# Charging_Circuit.net
KiCad netlist of a schematic drawn in EAGLE
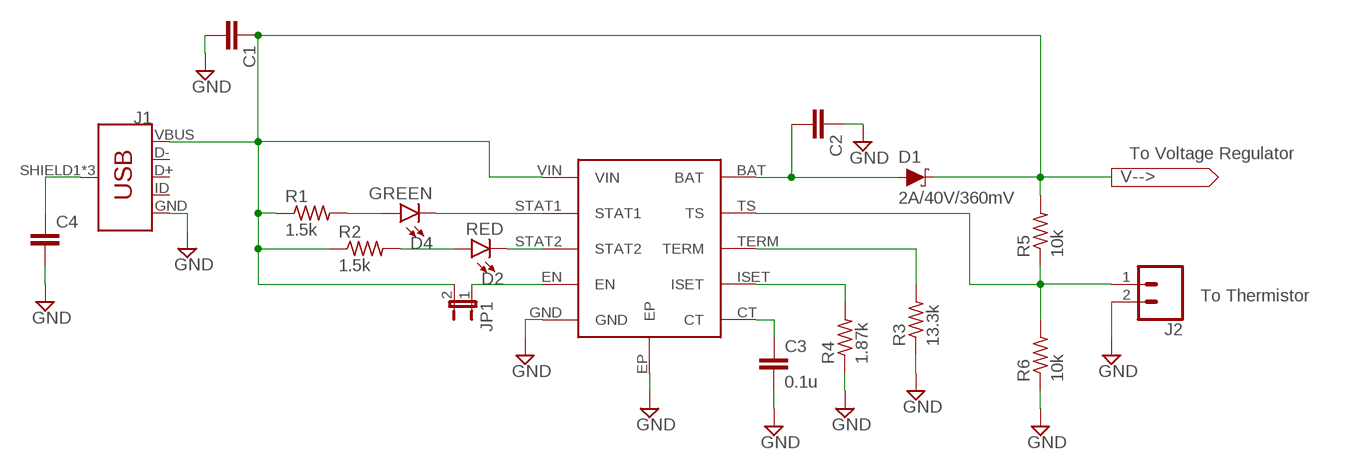
[diagram p0: schematic, sheet 1]

(export (version "E")
  (design (tool "Eeschema 10.0.6"))
  (components
    (comp (ref "C1")
      (value "C-EU025-024X044")
      (footprint "eagle-import:C025-024X044")
      (libsource (lib "eagle-import") (part "C-EU025-024X044"))
    )
    (comp (ref "C2")
      (value "C-EU025-024X044")
      (footprint "eagle-import:C025-024X044")
      (libsource (lib "eagle-import") (part "C-EU025-024X044"))
    )
    (comp (ref "C3")
      (value "0.1u")
      (footprint "eagle-import:C025-024X044")
      (libsource (lib "eagle-import") (part "C-EU025-024X044"))
    )
    (comp (ref "C4")
      (value "C-EU025-024X044")
      (footprint "eagle-import:C025-024X044")
      (libsource (lib "eagle-import") (part "C-EU025-024X044"))
    )
    (comp (ref "D1")
      (value "2A/40V/360mV")
      (footprint "eagle-import:SMA-DIODE")
      (libsource (lib "eagle-import") (part "DIODE-SCHOTTKY-B340A"))
    )
    (comp (ref "D2")
      (value "RED")
      (footprint "eagle-import:LED-1206")
      (libsource (lib "eagle-import") (part "LED-RED1206"))
    )
    (comp (ref "D4")
      (value "GREEN")
      (footprint "eagle-import:LED-1206")
      (libsource (lib "eagle-import") (part "LED-GREEN1206"))
    )
    (comp (ref "J1")
      (value "USB_MICRO-BREDUCED_PASTE")
      (footprint "eagle-import:USB-B-MICRO-SMD_RED_PASTE")
      (libsource (lib "eagle-import") (part "USB_MICRO-BREDUCED_PASTE"))
    )
    (comp (ref "J2")
      (value "CONN_02")
      (footprint "eagle-import:1X02")
      (libsource (lib "eagle-import") (part "CONN_02"))
    )
    (comp (ref "JP1")
      (value "JUMPER-2PTH")
      (footprint "eagle-import:1X02")
      (libsource (lib "eagle-import") (part "JUMPER-2PTH"))
    )
    (comp (ref "R1")
      (value "1.5k")
      (footprint "eagle-import:0204_5")
      (libsource (lib "eagle-import") (part "R-US_0204/5"))
    )
    (comp (ref "R2")
      (value "1.5k")
      (footprint "eagle-import:0204_5")
      (libsource (lib "eagle-import") (part "R-US_0204/5"))
    )
    (comp (ref "R3")
      (value "13.3k")
      (footprint "eagle-import:0204_5")
      (libsource (lib "eagle-import") (part "R-US_0204/5"))
    )
    (comp (ref "R4")
      (value "1.87k")
      (footprint "eagle-import:0204_5")
      (libsource (lib "eagle-import") (part "R-US_0204/5"))
    )
    (comp (ref "R5")
      (value "10k")
      (footprint "eagle-import:0204_5")
      (libsource (lib "eagle-import") (part "R-US_0204/5"))
    )
    (comp (ref "R6")
      (value "10k")
      (footprint "eagle-import:0204_5")
      (libsource (lib "eagle-import") (part "R-US_0204/5"))
    )
    (comp (ref "U$1")
      (value "AAT3693")
      (footprint "eagle-import:IDH-AA-T1")
      (libsource (lib "eagle-import") (part "AAT3693"))
    )
  )
  (nets
    (net (code "1") (name "GND") (class "Default")
      (node (ref "C1") (pin "2") (pinfunction "2_2") (pintype "passive"))
      (node (ref "C2") (pin "1") (pinfunction "1_1") (pintype "passive"))
      (node (ref "C3") (pin "2") (pinfunction "2_2") (pintype "passive"))
      (node (ref "C4") (pin "2") (pinfunction "2_2") (pintype "passive"))
      (node (ref "J1") (pin "GND") (pinfunction "GND_GND") (pintype "power_in"))
      (node (ref "J2") (pin "2") (pinfunction "2_2") (pintype "passive"))
      (node (ref "R3") (pin "1") (pinfunction "1_1") (pintype "passive"))
      (node (ref "R4") (pin "1") (pinfunction "1_1") (pintype "passive"))
      (node (ref "R6") (pin "1") (pinfunction "1_1") (pintype "passive"))
      (node (ref "U$1") (pin "EP") (pinfunction "EP_EP") (pintype "bidirectional"))
      (node (ref "U$1") (pin "GND") (pinfunction "GND_GND") (pintype "bidirectional"))
    )
    (net (code "2") (name "Net-(C1-Pad1)") (class "Default")
      (node (ref "C1") (pin "1") (pinfunction "1_1") (pintype "passive"))
      (node (ref "D1") (pin "C") (pinfunction "C_C") (pintype "passive"))
      (node (ref "J1") (pin "VBUS") (pinfunction "VBUS_VBUS") (pintype "power_in"))
      (node (ref "JP1") (pin "2") (pinfunction "2_2") (pintype "passive"))
      (node (ref "R1") (pin "1") (pinfunction "1_1") (pintype "passive"))
      (node (ref "R2") (pin "1") (pinfunction "1_1") (pintype "passive"))
      (node (ref "R5") (pin "2") (pinfunction "2_2") (pintype "passive"))
      (node (ref "U$1") (pin "VIN") (pinfunction "VIN_VIN") (pintype "bidirectional"))
    )
    (net (code "3") (name "Net-(C2-Pad2)") (class "Default")
      (node (ref "C2") (pin "2") (pinfunction "2_2") (pintype "passive"))
      (node (ref "D1") (pin "A") (pinfunction "A_A") (pintype "passive"))
      (node (ref "U$1") (pin "BAT") (pinfunction "BAT_BAT") (pintype "bidirectional"))
    )
    (net (code "4") (name "Net-(C3-Pad1)") (class "Default")
      (node (ref "C3") (pin "1") (pinfunction "1_1") (pintype "passive"))
      (node (ref "U$1") (pin "CT") (pinfunction "CT_CT") (pintype "bidirectional"))
    )
    (net (code "5") (name "Net-(C4-Pad1)") (class "Default")
      (node (ref "C4") (pin "1") (pinfunction "1_1") (pintype "passive"))
      (node (ref "J1") (pin "SHIELD1") (pinfunction "SHIELD_SHIELD1") (pintype "bidirectional"))
      (node (ref "J1") (pin "SHIELD2") (pinfunction "SHIELD_SHIELD2") (pintype "bidirectional"))
      (node (ref "J1") (pin "SHIELD3") (pinfunction "SHIELD_SHIELD3") (pintype "bidirectional"))
    )
    (net (code "6") (name "Net-(D2-PadA)") (class "Default")
      (node (ref "D2") (pin "A") (pinfunction "A_A") (pintype "passive"))
      (node (ref "R2") (pin "2") (pinfunction "2_2") (pintype "passive"))
    )
    (net (code "7") (name "Net-(D2-PadC)") (class "Default")
      (node (ref "D2") (pin "C") (pinfunction "C_C") (pintype "passive"))
      (node (ref "U$1") (pin "STAT2") (pinfunction "STAT2_STAT2") (pintype "bidirectional"))
    )
    (net (code "8") (name "Net-(D4-PadA)") (class "Default")
      (node (ref "D4") (pin "A") (pinfunction "A_A") (pintype "passive"))
      (node (ref "R1") (pin "2") (pinfunction "2_2") (pintype "passive"))
    )
    (net (code "9") (name "Net-(D4-PadC)") (class "Default")
      (node (ref "D4") (pin "C") (pinfunction "C_C") (pintype "passive"))
      (node (ref "U$1") (pin "STAT1") (pinfunction "STAT1_STAT1") (pintype "bidirectional"))
    )
    (net (code "10") (name "Net-(J2-Pad1)") (class "Default")
      (node (ref "J2") (pin "1") (pinfunction "1_1") (pintype "passive"))
      (node (ref "R5") (pin "1") (pinfunction "1_1") (pintype "passive"))
      (node (ref "R6") (pin "2") (pinfunction "2_2") (pintype "passive"))
      (node (ref "U$1") (pin "TS") (pinfunction "TS_TS") (pintype "bidirectional"))
    )
    (net (code "11") (name "Net-(JP1-Pad1)") (class "Default")
      (node (ref "JP1") (pin "1") (pinfunction "1_1") (pintype "passive"))
      (node (ref "U$1") (pin "EN") (pinfunction "EN_EN") (pintype "bidirectional"))
    )
    (net (code "12") (name "Net-(R3-Pad2)") (class "Default")
      (node (ref "R3") (pin "2") (pinfunction "2_2") (pintype "passive"))
      (node (ref "U$1") (pin "TERM") (pinfunction "TERM_TERM") (pintype "bidirectional"))
    )
    (net (code "13") (name "Net-(R4-Pad2)") (class "Default")
      (node (ref "R4") (pin "2") (pinfunction "2_2") (pintype "passive"))
      (node (ref "U$1") (pin "ISET") (pinfunction "ISET_ISET") (pintype "bidirectional"))
    )
    (net (code "14") (name "unconnected-(J1-PadD+)") (class "Default")
      (node (ref "J1") (pin "D+") (pinfunction "D+_D+") (pintype "bidirectional"))
    )
    (net (code "15") (name "unconnected-(J1-PadD-)") (class "Default")
      (node (ref "J1") (pin "D-") (pinfunction "D-_D-") (pintype "bidirectional"))
    )
    (net (code "16") (name "unconnected-(J1-PadID)") (class "Default")
      (node (ref "J1") (pin "ID") (pinfunction "ID_ID") (pintype "bidirectional"))
    )
  )
)
